# FPGA_RGMII_Misc.net
KiCad netlist of a schematic drawn in Altium Designer
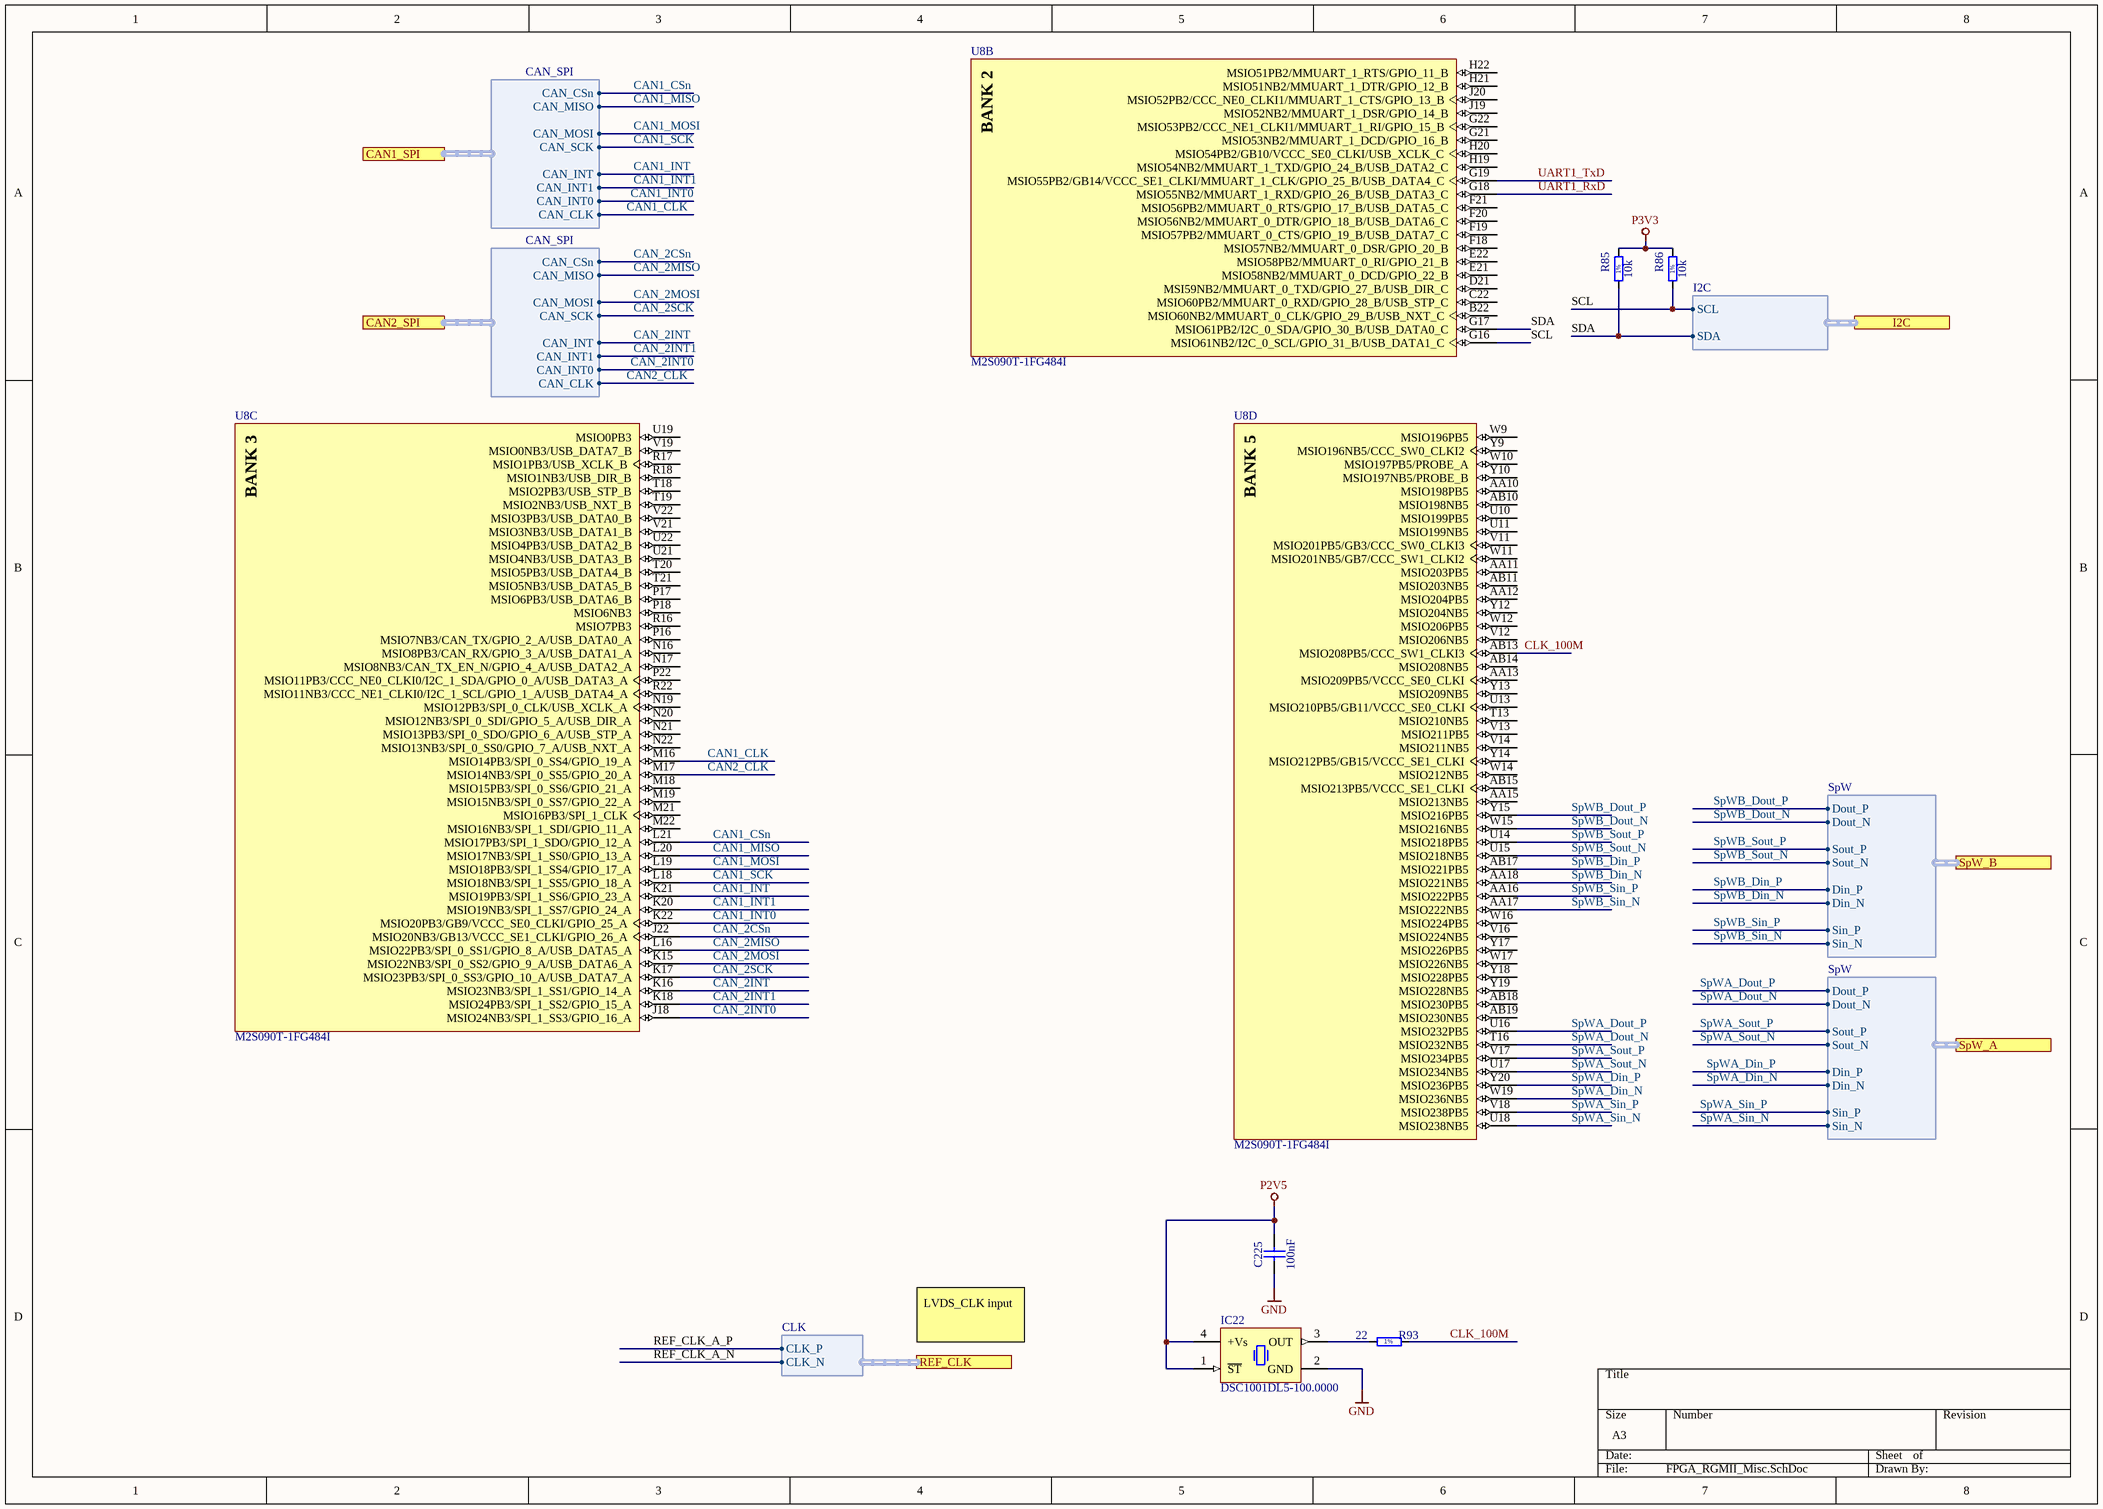
[diagram p0: FPGA_RGMII_Misc.SchDoc]

(export (version "E")
  (design (tool "Eeschema 10.0.6"))
  (components
    (comp (ref "C225")
      (value "100nF")
      (footprint "CAPC0603X33N")
      (description "Non-polarised capacitor")
      (fields
        (field (name "PART NUMBER") "CC0201_100NF_6.3V_10%_X5R")
        (field (name "MANUFACTURER") "GENERIC")
        (field (name "AUTHOR") "CERN DEM JLC")
      )
      (libsource (lib "Capacitors") (part "Capacitor - non polarized"))
    )
    (comp (ref "IC22")
      (value "DSC1001DL5-100.0000")
      (footprint "OSC_MICREL_2520")
      (description "MEMS 100MHz oscillator")
      (fields (field (name "MANUFACTURER") "Micrel"))
      (libsource (lib "LIBRARY_SCH") (part "OSC_DSC1001DL5-100.0000"))
    )
    (comp (ref "R85")
      (value "10k")
      (footprint "RESC1005X40N")
      (description "Resistor - 1%")
      (fields
        (field (name "MANUFACTURER PART NUMBER") "R0402_10K_1%_0.0625W_100PPM")
        (field (name "MANUFACTURER") "GENERIC")
        (field (name "AUTHOR") "CERN DEM JLC")
      )
      (libsource (lib "Resistors") (part "Resistor - 1%"))
    )
    (comp (ref "R86")
      (value "10k")
      (footprint "RESC1005X40N")
      (description "Resistor - 1%")
      (fields
        (field (name "MANUFACTURER PART NUMBER") "R0402_10K_1%_0.0625W_100PPM")
        (field (name "MANUFACTURER") "GENERIC")
        (field (name "AUTHOR") "CERN DEM JLC")
      )
      (libsource (lib "Resistors") (part "Resistor - 1%"))
    )
    (comp (ref "R93")
      (value "22")
      (footprint "RESC1005X40N")
      (description "Resistor - 1%")
      (fields
        (field (name "PART NUMBER") "R0402_22R_1%_0.0625W_100PPM")
        (field (name "POWER") "0.0625W")
        (field (name "AUTHOR") "CERN DEM JLC")
      )
      (libsource (lib "Resistors") (part "Resistor - 1%"))
    )
    (comp (ref "U8")
      (value "M2S090T-1FG484I")
      (footprint "MCSM-FG-484_V")
      (fields (field (name "MANUFACTURER") "Microsemi"))
      (libsource (lib "Altium Content Vault") (part "MCSM-M2S090T-BGA-484"))
    )
  )
  (nets
    (net (code "5") (name "/CAN1_CLK") (class "Default")
      (node (ref "U8") (pin "M16") (pinfunction "MSIO14PB3/SPI_0_SS4/GPIO_19_A_M16") (pintype "bidirectional"))
    )
    (net (code "6") (name "/CAN1_CSn") (class "Default")
      (node (ref "U8") (pin "L21") (pinfunction "MSIO17PB3/SPI_1_SDO/GPIO_12_A_L21") (pintype "bidirectional"))
    )
    (net (code "7") (name "/CAN1_INT") (class "Default")
      (node (ref "U8") (pin "K21") (pinfunction "MSIO19PB3/SPI_1_SS6/GPIO_23_A_K21") (pintype "bidirectional"))
    )
    (net (code "8") (name "/CAN1_INT0") (class "Default")
      (node (ref "U8") (pin "K22") (pinfunction "MSIO20PB3/GB9/VCCC_SE0_CLKI/GPIO_25_A_K22") (pintype "bidirectional"))
    )
    (net (code "9") (name "/CAN1_INT1") (class "Default")
      (node (ref "U8") (pin "K20") (pinfunction "MSIO19NB3/SPI_1_SS7/GPIO_24_A_K20") (pintype "bidirectional"))
    )
    (net (code "10") (name "/CAN1_MISO") (class "Default")
      (node (ref "U8") (pin "L20") (pinfunction "MSIO17NB3/SPI_1_SS0/GPIO_13_A_L20") (pintype "bidirectional"))
    )
    (net (code "11") (name "/CAN1_MOSI") (class "Default")
      (node (ref "U8") (pin "L19") (pinfunction "MSIO18PB3/SPI_1_SS4/GPIO_17_A_L19") (pintype "bidirectional"))
    )
    (net (code "12") (name "/CAN1_SCK") (class "Default")
      (node (ref "U8") (pin "L18") (pinfunction "MSIO18NB3/SPI_1_SS5/GPIO_18_A_L18") (pintype "bidirectional"))
    )
    (net (code "13") (name "/CAN2_CLK") (class "Default")
      (node (ref "U8") (pin "M17") (pinfunction "MSIO14NB3/SPI_0_SS5/GPIO_20_A_M17") (pintype "bidirectional"))
    )
    (net (code "14") (name "/CAN_2CSn") (class "Default")
      (node (ref "U8") (pin "J22") (pinfunction "MSIO20NB3/GB13/VCCC_SE1_CLKI/GPIO_26_A_J22") (pintype "bidirectional"))
    )
    (net (code "15") (name "/CAN_2INT") (class "Default")
      (node (ref "U8") (pin "K16") (pinfunction "MSIO23NB3/SPI_1_SS1/GPIO_14_A_K16") (pintype "bidirectional"))
    )
    (net (code "16") (name "/CAN_2INT0") (class "Default")
      (node (ref "U8") (pin "J18") (pinfunction "MSIO24NB3/SPI_1_SS3/GPIO_16_A_J18") (pintype "bidirectional"))
    )
    (net (code "17") (name "/CAN_2INT1") (class "Default")
      (node (ref "U8") (pin "K18") (pinfunction "MSIO24PB3/SPI_1_SS2/GPIO_15_A_K18") (pintype "bidirectional"))
    )
    (net (code "18") (name "/CAN_2MISO") (class "Default")
      (node (ref "U8") (pin "L16") (pinfunction "MSIO22PB3/SPI_0_SS1/GPIO_8_A/USB_DATA5_A_L16") (pintype "bidirectional"))
    )
    (net (code "19") (name "/CAN_2MOSI") (class "Default")
      (node (ref "U8") (pin "K15") (pinfunction "MSIO22NB3/SPI_0_SS2/GPIO_9_A/USB_DATA6_A_K15") (pintype "bidirectional"))
    )
    (net (code "20") (name "/CAN_2SCK") (class "Default")
      (node (ref "U8") (pin "K17") (pinfunction "MSIO23PB3/SPI_0_SS3/GPIO_10_A/USB_DATA7_A_K17") (pintype "bidirectional"))
    )
    (net (code "21") (name "/CLK_100M") (class "Default")
      (node (ref "R93") (pin "2") (pinfunction "2_2") (pintype "passive"))
      (node (ref "U8") (pin "AB13") (pinfunction "MSIO208PB5/CCC_SW1_CLKI3_AB13") (pintype "bidirectional"))
    )
    (net (code "24") (name "/SCL") (class "Default")
      (node (ref "R86") (pin "1") (pinfunction "1_1") (pintype "passive"))
      (node (ref "U8") (pin "G16") (pinfunction "MSIO61NB2/I2C_0_SCL/GPIO_31_B/USB_DATA1_C_G16") (pintype "bidirectional"))
    )
    (net (code "25") (name "/SDA") (class "Default")
      (node (ref "R85") (pin "1") (pinfunction "1_1") (pintype "passive"))
      (node (ref "U8") (pin "G17") (pinfunction "MSIO61PB2/I2C_0_SDA/GPIO_30_B/USB_DATA0_C_G17") (pintype "bidirectional"))
    )
    (net (code "26") (name "/SpWA_Din_N") (class "Default")
      (node (ref "U8") (pin "W19") (pinfunction "MSIO236NB5_W19") (pintype "bidirectional"))
    )
    (net (code "27") (name "/SpWA_Din_P") (class "Default")
      (node (ref "U8") (pin "Y20") (pinfunction "MSIO236PB5_Y20") (pintype "bidirectional"))
    )
    (net (code "28") (name "/SpWA_Dout_N") (class "Default")
      (node (ref "U8") (pin "T16") (pinfunction "MSIO232NB5_T16") (pintype "bidirectional"))
    )
    (net (code "29") (name "/SpWA_Dout_P") (class "Default")
      (node (ref "U8") (pin "U16") (pinfunction "MSIO232PB5_U16") (pintype "bidirectional"))
    )
    (net (code "30") (name "/SpWA_Sin_N") (class "Default")
      (node (ref "U8") (pin "U18") (pinfunction "MSIO238NB5_U18") (pintype "bidirectional"))
    )
    (net (code "31") (name "/SpWA_Sin_P") (class "Default")
      (node (ref "U8") (pin "V18") (pinfunction "MSIO238PB5_V18") (pintype "bidirectional"))
    )
    (net (code "32") (name "/SpWA_Sout_N") (class "Default")
      (node (ref "U8") (pin "U17") (pinfunction "MSIO234NB5_U17") (pintype "bidirectional"))
    )
    (net (code "33") (name "/SpWA_Sout_P") (class "Default")
      (node (ref "U8") (pin "V17") (pinfunction "MSIO234PB5_V17") (pintype "bidirectional"))
    )
    (net (code "34") (name "/SpWB_Din_N") (class "Default")
      (node (ref "U8") (pin "AA18") (pinfunction "MSIO221NB5_AA18") (pintype "bidirectional"))
    )
    (net (code "35") (name "/SpWB_Din_P") (class "Default")
      (node (ref "U8") (pin "AB17") (pinfunction "MSIO221PB5_AB17") (pintype "bidirectional"))
    )
    (net (code "36") (name "/SpWB_Dout_N") (class "Default")
      (node (ref "U8") (pin "W15") (pinfunction "MSIO216NB5_W15") (pintype "bidirectional"))
    )
    (net (code "37") (name "/SpWB_Dout_P") (class "Default")
      (node (ref "U8") (pin "Y15") (pinfunction "MSIO216PB5_Y15") (pintype "bidirectional"))
    )
    (net (code "38") (name "/SpWB_Sin_N") (class "Default")
      (node (ref "U8") (pin "AA17") (pinfunction "MSIO222NB5_AA17") (pintype "bidirectional"))
    )
    (net (code "39") (name "/SpWB_Sin_P") (class "Default")
      (node (ref "U8") (pin "AA16") (pinfunction "MSIO222PB5_AA16") (pintype "bidirectional"))
    )
    (net (code "40") (name "/SpWB_Sout_N") (class "Default")
      (node (ref "U8") (pin "U15") (pinfunction "MSIO218NB5_U15") (pintype "bidirectional"))
    )
    (net (code "41") (name "/SpWB_Sout_P") (class "Default")
      (node (ref "U8") (pin "U14") (pinfunction "MSIO218PB5_U14") (pintype "bidirectional"))
    )
    (net (code "42") (name "/UART1_RxD") (class "Default")
      (node (ref "U8") (pin "G18") (pinfunction "MSIO55NB2/MMUART_1_RXD/GPIO_26_B/USB_DATA3_C_G18") (pintype "bidirectional"))
    )
    (net (code "43") (name "/UART1_TxD") (class "Default")
      (node (ref "U8") (pin "G19") (pinfunction "MSIO55PB2/GB14/VCCC_SE1_CLKI/MMUART_1_CLK/GPIO_25_B/USB_DATA4_C_G19") (pintype "bidirectional"))
    )
    (net (code "48") (name "GND") (class "Default")
      (node (ref "C225") (pin "1") (pinfunction "1_1") (pintype "passive"))
      (node (ref "IC22") (pin "2") (pinfunction "GND_2") (pintype "power_in"))
    )
    (net (code "49") (name "Net-(IC22-OUT)") (class "Default")
      (node (ref "IC22") (pin "3") (pinfunction "OUT_3") (pintype "output"))
      (node (ref "R93") (pin "1") (pinfunction "1_1") (pintype "passive"))
    )
    (net (code "50") (name "P2V5") (class "Default")
      (node (ref "C225") (pin "2") (pinfunction "2_2") (pintype "passive"))
      (node (ref "IC22") (pin "1") (pinfunction "ST_1") (pintype "input"))
      (node (ref "IC22") (pin "4") (pinfunction "+Vs_4") (pintype "power_in"))
    )
    (net (code "51") (name "P3V3") (class "Default")
      (node (ref "R85") (pin "2") (pinfunction "2_2") (pintype "passive"))
      (node (ref "R86") (pin "2") (pinfunction "2_2") (pintype "passive"))
    )
    (net (code "52") (name "unconnected-(U8B-MSI59NB2{slash}MMUART_0_TXD{slash}GPIO_27_B{slash}USB_DIR_C-PadD21)") (class "Default")
      (node (ref "U8") (pin "D21") (pinfunction "MSI59NB2/MMUART_0_TXD/GPIO_27_B/USB_DIR_C_D21") (pintype "bidirectional"))
    )
    (net (code "53") (name "unconnected-(U8B-MSIO51NB2{slash}MMUART_1_DTR{slash}GPIO_12_B-PadH21)") (class "Default")
      (node (ref "U8") (pin "H21") (pinfunction "MSIO51NB2/MMUART_1_DTR/GPIO_12_B_H21") (pintype "bidirectional"))
    )
    (net (code "54") (name "unconnected-(U8B-MSIO51PB2{slash}MMUART_1_RTS{slash}GPIO_11_B-PadH22)") (class "Default")
      (node (ref "U8") (pin "H22") (pinfunction "MSIO51PB2/MMUART_1_RTS/GPIO_11_B_H22") (pintype "bidirectional"))
    )
    (net (code "55") (name "unconnected-(U8B-MSIO52NB2{slash}MMUART_1_DSR{slash}GPIO_14_B-PadJ19)") (class "Default")
      (node (ref "U8") (pin "J19") (pinfunction "MSIO52NB2/MMUART_1_DSR/GPIO_14_B_J19") (pintype "bidirectional"))
    )
    (net (code "56") (name "unconnected-(U8B-MSIO52PB2{slash}CCC_NE0_CLKI1{slash}MMUART_1_CTS{slash}GPIO_13_B-PadJ20)") (class "Default")
      (node (ref "U8") (pin "J20") (pinfunction "MSIO52PB2/CCC_NE0_CLKI1/MMUART_1_CTS/GPIO_13_B_J20") (pintype "bidirectional"))
    )
    (net (code "57") (name "unconnected-(U8B-MSIO53NB2{slash}MMUART_1_DCD{slash}GPIO_16_B-PadG21)") (class "Default")
      (node (ref "U8") (pin "G21") (pinfunction "MSIO53NB2/MMUART_1_DCD/GPIO_16_B_G21") (pintype "bidirectional"))
    )
    (net (code "58") (name "unconnected-(U8B-MSIO53PB2{slash}CCC_NE1_CLKI1{slash}MMUART_1_RI{slash}GPIO_15_B-PadG22)") (class "Default")
      (node (ref "U8") (pin "G22") (pinfunction "MSIO53PB2/CCC_NE1_CLKI1/MMUART_1_RI/GPIO_15_B_G22") (pintype "bidirectional"))
    )
    (net (code "59") (name "unconnected-(U8B-MSIO54NB2{slash}MMUART_1_TXD{slash}GPIO_24_B{slash}USB_DATA2_C-PadH19)") (class "Default")
      (node (ref "U8") (pin "H19") (pinfunction "MSIO54NB2/MMUART_1_TXD/GPIO_24_B/USB_DATA2_C_H19") (pintype "bidirectional"))
    )
    (net (code "60") (name "unconnected-(U8B-MSIO54PB2{slash}GB10{slash}VCCC_SE0_CLKI{slash}USB_XCLK_C-PadH20)") (class "Default")
      (node (ref "U8") (pin "H20") (pinfunction "MSIO54PB2/GB10/VCCC_SE0_CLKI/USB_XCLK_C_H20") (pintype "bidirectional"))
    )
    (net (code "61") (name "unconnected-(U8B-MSIO56NB2{slash}MMUART_0_DTR{slash}GPIO_18_B{slash}USB_DATA6_C-PadF20)") (class "Default")
      (node (ref "U8") (pin "F20") (pinfunction "MSIO56NB2/MMUART_0_DTR/GPIO_18_B/USB_DATA6_C_F20") (pintype "bidirectional"))
    )
    (net (code "62") (name "unconnected-(U8B-MSIO56PB2{slash}MMUART_0_RTS{slash}GPIO_17_B{slash}USB_DATA5_C-PadF21)") (class "Default")
      (node (ref "U8") (pin "F21") (pinfunction "MSIO56PB2/MMUART_0_RTS/GPIO_17_B/USB_DATA5_C_F21") (pintype "bidirectional"))
    )
    (net (code "63") (name "unconnected-(U8B-MSIO57NB2{slash}MMUART_0_DSR{slash}GPIO_20_B-PadF18)") (class "Default")
      (node (ref "U8") (pin "F18") (pinfunction "MSIO57NB2/MMUART_0_DSR/GPIO_20_B_F18") (pintype "bidirectional"))
    )
    (net (code "64") (name "unconnected-(U8B-MSIO57PB2{slash}MMUART_0_CTS{slash}GPIO_19_B{slash}USB_DATA7_C-PadF19)") (class "Default")
      (node (ref "U8") (pin "F19") (pinfunction "MSIO57PB2/MMUART_0_CTS/GPIO_19_B/USB_DATA7_C_F19") (pintype "bidirectional"))
    )
    (net (code "65") (name "unconnected-(U8B-MSIO58NB2{slash}MMUART_0_DCD{slash}GPIO_22_B-PadE21)") (class "Default")
      (node (ref "U8") (pin "E21") (pinfunction "MSIO58NB2/MMUART_0_DCD/GPIO_22_B_E21") (pintype "bidirectional"))
    )
    (net (code "66") (name "unconnected-(U8B-MSIO58PB2{slash}MMUART_0_RI{slash}GPIO_21_B-PadE22)") (class "Default")
      (node (ref "U8") (pin "E22") (pinfunction "MSIO58PB2/MMUART_0_RI/GPIO_21_B_E22") (pintype "bidirectional"))
    )
    (net (code "67") (name "unconnected-(U8B-MSIO60NB2{slash}MMUART_0_CLK{slash}GPIO_29_B{slash}USB_NXT_C-PadB22)") (class "Default")
      (node (ref "U8") (pin "B22") (pinfunction "MSIO60NB2/MMUART_0_CLK/GPIO_29_B/USB_NXT_C_B22") (pintype "bidirectional"))
    )
    (net (code "68") (name "unconnected-(U8B-MSIO60PB2{slash}MMUART_0_RXD{slash}GPIO_28_B{slash}USB_STP_C-PadC22)") (class "Default")
      (node (ref "U8") (pin "C22") (pinfunction "MSIO60PB2/MMUART_0_RXD/GPIO_28_B/USB_STP_C_C22") (pintype "bidirectional"))
    )
    (net (code "69") (name "unconnected-(U8C-MSIO0NB3{slash}USB_DATA7_B-PadV19)") (class "Default")
      (node (ref "U8") (pin "V19") (pinfunction "MSIO0NB3/USB_DATA7_B_V19") (pintype "bidirectional"))
    )
    (net (code "70") (name "unconnected-(U8C-MSIO0PB3-PadU19)") (class "Default")
      (node (ref "U8") (pin "U19") (pinfunction "MSIO0PB3_U19") (pintype "bidirectional"))
    )
    (net (code "71") (name "unconnected-(U8C-MSIO1NB3{slash}USB_DIR_B-PadR18)") (class "Default")
      (node (ref "U8") (pin "R18") (pinfunction "MSIO1NB3/USB_DIR_B_R18") (pintype "bidirectional"))
    )
    (net (code "72") (name "unconnected-(U8C-MSIO1PB3{slash}USB_XCLK_B-PadR17)") (class "Default")
      (node (ref "U8") (pin "R17") (pinfunction "MSIO1PB3/USB_XCLK_B_R17") (pintype "bidirectional"))
    )
    (net (code "73") (name "unconnected-(U8C-MSIO2NB3{slash}USB_NXT_B-PadT19)") (class "Default")
      (node (ref "U8") (pin "T19") (pinfunction "MSIO2NB3/USB_NXT_B_T19") (pintype "bidirectional"))
    )
    (net (code "74") (name "unconnected-(U8C-MSIO2PB3{slash}USB_STP_B-PadT18)") (class "Default")
      (node (ref "U8") (pin "T18") (pinfunction "MSIO2PB3/USB_STP_B_T18") (pintype "bidirectional"))
    )
    (net (code "75") (name "unconnected-(U8C-MSIO3NB3{slash}USB_DATA1_B-PadV21)") (class "Default")
      (node (ref "U8") (pin "V21") (pinfunction "MSIO3NB3/USB_DATA1_B_V21") (pintype "bidirectional"))
    )
    (net (code "76") (name "unconnected-(U8C-MSIO3PB3{slash}USB_DATA0_B-PadV22)") (class "Default")
      (node (ref "U8") (pin "V22") (pinfunction "MSIO3PB3/USB_DATA0_B_V22") (pintype "bidirectional"))
    )
    (net (code "77") (name "unconnected-(U8C-MSIO4NB3{slash}USB_DATA3_B-PadU21)") (class "Default")
      (node (ref "U8") (pin "U21") (pinfunction "MSIO4NB3/USB_DATA3_B_U21") (pintype "bidirectional"))
    )
    (net (code "78") (name "unconnected-(U8C-MSIO4PB3{slash}USB_DATA2_B-PadU22)") (class "Default")
      (node (ref "U8") (pin "U22") (pinfunction "MSIO4PB3/USB_DATA2_B_U22") (pintype "bidirectional"))
    )
    (net (code "79") (name "unconnected-(U8C-MSIO5NB3{slash}USB_DATA5_B-PadT21)") (class "Default")
      (node (ref "U8") (pin "T21") (pinfunction "MSIO5NB3/USB_DATA5_B_T21") (pintype "bidirectional"))
    )
    (net (code "80") (name "unconnected-(U8C-MSIO5PB3{slash}USB_DATA4_B-PadT20)") (class "Default")
      (node (ref "U8") (pin "T20") (pinfunction "MSIO5PB3/USB_DATA4_B_T20") (pintype "bidirectional"))
    )
    (net (code "81") (name "unconnected-(U8C-MSIO6NB3-PadP18)") (class "Default")
      (node (ref "U8") (pin "P18") (pinfunction "MSIO6NB3_P18") (pintype "bidirectional"))
    )
    (net (code "82") (name "unconnected-(U8C-MSIO6PB3{slash}USB_DATA6_B-PadP17)") (class "Default")
      (node (ref "U8") (pin "P17") (pinfunction "MSIO6PB3/USB_DATA6_B_P17") (pintype "bidirectional"))
    )
    (net (code "83") (name "unconnected-(U8C-MSIO7NB3{slash}CAN_TX{slash}GPIO_2_A{slash}USB_DATA0_A-PadP16)") (class "Default")
      (node (ref "U8") (pin "P16") (pinfunction "MSIO7NB3/CAN_TX/GPIO_2_A/USB_DATA0_A_P16") (pintype "bidirectional"))
    )
    (net (code "84") (name "unconnected-(U8C-MSIO7PB3-PadR16)") (class "Default")
      (node (ref "U8") (pin "R16") (pinfunction "MSIO7PB3_R16") (pintype "bidirectional"))
    )
    (net (code "85") (name "unconnected-(U8C-MSIO8NB3{slash}CAN_TX_EN_N{slash}GPIO_4_A{slash}USB_DATA2_A-PadN17)") (class "Default")
      (node (ref "U8") (pin "N17") (pinfunction "MSIO8NB3/CAN_TX_EN_N/GPIO_4_A/USB_DATA2_A_N17") (pintype "bidirectional"))
    )
    (net (code "86") (name "unconnected-(U8C-MSIO8PB3{slash}CAN_RX{slash}GPIO_3_A{slash}USB_DATA1_A-PadN16)") (class "Default")
      (node (ref "U8") (pin "N16") (pinfunction "MSIO8PB3/CAN_RX/GPIO_3_A/USB_DATA1_A_N16") (pintype "bidirectional"))
    )
    (net (code "87") (name "unconnected-(U8C-MSIO11NB3{slash}CCC_NE1_CLKI0{slash}I2C_1_SCL{slash}GPIO_1_A{slash}USB_DATA4_A-PadR22)") (class "Default")
      (node (ref "U8") (pin "R22") (pinfunction "MSIO11NB3/CCC_NE1_CLKI0/I2C_1_SCL/GPIO_1_A/USB_DATA4_A_R22") (pintype "bidirectional"))
    )
    (net (code "88") (name "unconnected-(U8C-MSIO11PB3{slash}CCC_NE0_CLKI0{slash}I2C_1_SDA{slash}GPIO_0_A{slash}USB_DATA3_A-PadP22)") (class "Default")
      (node (ref "U8") (pin "P22") (pinfunction "MSIO11PB3/CCC_NE0_CLKI0/I2C_1_SDA/GPIO_0_A/USB_DATA3_A_P22") (pintype "bidirectional"))
    )
    (net (code "89") (name "unconnected-(U8C-MSIO12NB3{slash}SPI_0_SDI{slash}GPIO_5_A{slash}USB_DIR_A-PadN20)") (class "Default")
      (node (ref "U8") (pin "N20") (pinfunction "MSIO12NB3/SPI_0_SDI/GPIO_5_A/USB_DIR_A_N20") (pintype "bidirectional"))
    )
    (net (code "90") (name "unconnected-(U8C-MSIO12PB3{slash}SPI_0_CLK{slash}USB_XCLK_A-PadN19)") (class "Default")
      (node (ref "U8") (pin "N19") (pinfunction "MSIO12PB3/SPI_0_CLK/USB_XCLK_A_N19") (pintype "bidirectional"))
    )
    (net (code "91") (name "unconnected-(U8C-MSIO13NB3{slash}SPI_0_SS0{slash}GPIO_7_A{slash}USB_NXT_A-PadN22)") (class "Default")
      (node (ref "U8") (pin "N22") (pinfunction "MSIO13NB3/SPI_0_SS0/GPIO_7_A/USB_NXT_A_N22") (pintype "bidirectional"))
    )
    (net (code "92") (name "unconnected-(U8C-MSIO13PB3{slash}SPI_0_SDO{slash}GPIO_6_A{slash}USB_STP_A-PadN21)") (class "Default")
      (node (ref "U8") (pin "N21") (pinfunction "MSIO13PB3/SPI_0_SDO/GPIO_6_A/USB_STP_A_N21") (pintype "bidirectional"))
    )
    (net (code "93") (name "unconnected-(U8C-MSIO15NB3{slash}SPI_0_SS7{slash}GPIO_22_A-PadM19)") (class "Default")
      (node (ref "U8") (pin "M19") (pinfunction "MSIO15NB3/SPI_0_SS7/GPIO_22_A_M19") (pintype "bidirectional"))
    )
    (net (code "94") (name "unconnected-(U8C-MSIO15PB3{slash}SPI_0_SS6{slash}GPIO_21_A-PadM18)") (class "Default")
      (node (ref "U8") (pin "M18") (pinfunction "MSIO15PB3/SPI_0_SS6/GPIO_21_A_M18") (pintype "bidirectional"))
    )
    (net (code "95") (name "unconnected-(U8C-MSIO16NB3{slash}SPI_1_SDI{slash}GPIO_11_A-PadM22)") (class "Default")
      (node (ref "U8") (pin "M22") (pinfunction "MSIO16NB3/SPI_1_SDI/GPIO_11_A_M22") (pintype "bidirectional"))
    )
    (net (code "96") (name "unconnected-(U8C-MSIO16PB3{slash}SPI_1_CLK-PadM21)") (class "Default")
      (node (ref "U8") (pin "M21") (pinfunction "MSIO16PB3/SPI_1_CLK_M21") (pintype "bidirectional"))
    )
    (net (code "97") (name "unconnected-(U8D-MSIO196NB5{slash}CCC_SW0_CLKI2-PadY9)") (class "Default")
      (node (ref "U8") (pin "Y9") (pinfunction "MSIO196NB5/CCC_SW0_CLKI2_Y9") (pintype "bidirectional"))
    )
    (net (code "98") (name "unconnected-(U8D-MSIO196PB5-PadW9)") (class "Default")
      (node (ref "U8") (pin "W9") (pinfunction "MSIO196PB5_W9") (pintype "bidirectional"))
    )
    (net (code "99") (name "unconnected-(U8D-MSIO197NB5{slash}PROBE_B-PadY10)") (class "Default")
      (node (ref "U8") (pin "Y10") (pinfunction "MSIO197NB5/PROBE_B_Y10") (pintype "bidirectional"))
    )
    (net (code "100") (name "unconnected-(U8D-MSIO197PB5{slash}PROBE_A-PadW10)") (class "Default")
      (node (ref "U8") (pin "W10") (pinfunction "MSIO197PB5/PROBE_A_W10") (pintype "bidirectional"))
    )
    (net (code "101") (name "unconnected-(U8D-MSIO198NB5-PadAB10)") (class "Default")
      (node (ref "U8") (pin "AB10") (pinfunction "MSIO198NB5_AB10") (pintype "bidirectional"))
    )
    (net (code "102") (name "unconnected-(U8D-MSIO198PB5-PadAA10)") (class "Default")
      (node (ref "U8") (pin "AA10") (pinfunction "MSIO198PB5_AA10") (pintype "bidirectional"))
    )
    (net (code "103") (name "unconnected-(U8D-MSIO199NB5-PadU11)") (class "Default")
      (node (ref "U8") (pin "U11") (pinfunction "MSIO199NB5_U11") (pintype "bidirectional"))
    )
    (net (code "104") (name "unconnected-(U8D-MSIO199PB5-PadU10)") (class "Default")
      (node (ref "U8") (pin "U10") (pinfunction "MSIO199PB5_U10") (pintype "bidirectional"))
    )
    (net (code "105") (name "unconnected-(U8D-MSIO201NB5{slash}GB7{slash}CCC_SW1_CLKI2-PadW11)") (class "Default")
      (node (ref "U8") (pin "W11") (pinfunction "MSIO201NB5/GB7/CCC_SW1_CLKI2_W11") (pintype "bidirectional"))
    )
    (net (code "106") (name "unconnected-(U8D-MSIO201PB5{slash}GB3{slash}CCC_SW0_CLKI3-PadV11)") (class "Default")
      (node (ref "U8") (pin "V11") (pinfunction "MSIO201PB5/GB3/CCC_SW0_CLKI3_V11") (pintype "bidirectional"))
    )
    (net (code "107") (name "unconnected-(U8D-MSIO203NB5-PadAB11)") (class "Default")
      (node (ref "U8") (pin "AB11") (pinfunction "MSIO203NB5_AB11") (pintype "bidirectional"))
    )
    (net (code "108") (name "unconnected-(U8D-MSIO203PB5-PadAA11)") (class "Default")
      (node (ref "U8") (pin "AA11") (pinfunction "MSIO203PB5_AA11") (pintype "bidirectional"))
    )
    (net (code "109") (name "unconnected-(U8D-MSIO204NB5-PadY12)") (class "Default")
      (node (ref "U8") (pin "Y12") (pinfunction "MSIO204NB5_Y12") (pintype "bidirectional"))
    )
    (net (code "110") (name "unconnected-(U8D-MSIO204PB5-PadAA12)") (class "Default")
      (node (ref "U8") (pin "AA12") (pinfunction "MSIO204PB5_AA12") (pintype "bidirectional"))
    )
    (net (code "111") (name "unconnected-(U8D-MSIO206NB5-PadV12)") (class "Default")
      (node (ref "U8") (pin "V12") (pinfunction "MSIO206NB5_V12") (pintype "bidirectional"))
    )
    (net (code "112") (name "unconnected-(U8D-MSIO206PB5-PadW12)") (class "Default")
      (node (ref "U8") (pin "W12") (pinfunction "MSIO206PB5_W12") (pintype "bidirectional"))
    )
    (net (code "113") (name "unconnected-(U8D-MSIO208NB5-PadAB14)") (class "Default")
      (node (ref "U8") (pin "AB14") (pinfunction "MSIO208NB5_AB14") (pintype "bidirectional"))
    )
    (net (code "114") (name "unconnected-(U8D-MSIO209NB5-PadY13)") (class "Default")
      (node (ref "U8") (pin "Y13") (pinfunction "MSIO209NB5_Y13") (pintype "bidirectional"))
    )
    (net (code "115") (name "unconnected-(U8D-MSIO209PB5{slash}VCCC_SE0_CLKI-PadAA13)") (class "Default")
      (node (ref "U8") (pin "AA13") (pinfunction "MSIO209PB5/VCCC_SE0_CLKI_AA13") (pintype "bidirectional"))
    )
    (net (code "116") (name "unconnected-(U8D-MSIO210NB5-PadT13)") (class "Default")
      (node (ref "U8") (pin "T13") (pinfunction "MSIO210NB5_T13") (pintype "bidirectional"))
    )
    (net (code "117") (name "unconnected-(U8D-MSIO210PB5{slash}GB11{slash}VCCC_SE0_CLKI-PadU13)") (class "Default")
      (node (ref "U8") (pin "U13") (pinfunction "MSIO210PB5/GB11/VCCC_SE0_CLKI_U13") (pintype "bidirectional"))
    )
    (net (code "118") (name "unconnected-(U8D-MSIO211NB5-PadV14)") (class "Default")
      (node (ref "U8") (pin "V14") (pinfunction "MSIO211NB5_V14") (pintype "bidirectional"))
    )
    (net (code "119") (name "unconnected-(U8D-MSIO211PB5-PadV13)") (class "Default")
      (node (ref "U8") (pin "V13") (pinfunction "MSIO211PB5_V13") (pintype "bidirectional"))
    )
    (net (code "120") (name "unconnected-(U8D-MSIO212NB5-PadW14)") (class "Default")
      (node (ref "U8") (pin "W14") (pinfunction "MSIO212NB5_W14") (pintype "bidirectional"))
    )
    (net (code "121") (name "unconnected-(U8D-MSIO212PB5{slash}GB15{slash}VCCC_SE1_CLKI-PadY14)") (class "Default")
      (node (ref "U8") (pin "Y14") (pinfunction "MSIO212PB5/GB15/VCCC_SE1_CLKI_Y14") (pintype "bidirectional"))
    )
    (net (code "122") (name "unconnected-(U8D-MSIO213NB5-PadAA15)") (class "Default")
      (node (ref "U8") (pin "AA15") (pinfunction "MSIO213NB5_AA15") (pintype "bidirectional"))
    )
    (net (code "123") (name "unconnected-(U8D-MSIO213PB5{slash}VCCC_SE1_CLKI-PadAB15)") (class "Default")
      (node (ref "U8") (pin "AB15") (pinfunction "MSIO213PB5/VCCC_SE1_CLKI_AB15") (pintype "bidirectional"))
    )
    (net (code "124") (name "unconnected-(U8D-MSIO224NB5-PadV16)") (class "Default")
      (node (ref "U8") (pin "V16") (pinfunction "MSIO224NB5_V16") (pintype "bidirectional"))
    )
    (net (code "125") (name "unconnected-(U8D-MSIO224PB5-PadW16)") (class "Default")
      (node (ref "U8") (pin "W16") (pinfunction "MSIO224PB5_W16") (pintype "bidirectional"))
    )
    (net (code "126") (name "unconnected-(U8D-MSIO226NB5-PadW17)") (class "Default")
      (node (ref "U8") (pin "W17") (pinfunction "MSIO226NB5_W17") (pintype "bidirectional"))
    )
    (net (code "127") (name "unconnected-(U8D-MSIO226PB5-PadY17)") (class "Default")
      (node (ref "U8") (pin "Y17") (pinfunction "MSIO226PB5_Y17") (pintype "bidirectional"))
    )
    (net (code "128") (name "unconnected-(U8D-MSIO228NB5-PadY19)") (class "Default")
      (node (ref "U8") (pin "Y19") (pinfunction "MSIO228NB5_Y19") (pintype "bidirectional"))
    )
    (net (code "129") (name "unconnected-(U8D-MSIO228PB5-PadY18)") (class "Default")
      (node (ref "U8") (pin "Y18") (pinfunction "MSIO228PB5_Y18") (pintype "bidirectional"))
    )
    (net (code "130") (name "unconnected-(U8D-MSIO230NB5-PadAB19)") (class "Default")
      (node (ref "U8") (pin "AB19") (pinfunction "MSIO230NB5_AB19") (pintype "bidirectional"))
    )
    (net (code "131") (name "unconnected-(U8D-MSIO230PB5-PadAB18)") (class "Default")
      (node (ref "U8") (pin "AB18") (pinfunction "MSIO230PB5_AB18") (pintype "bidirectional"))
    )
  )
)
